# CCS811_breakout.net
KiCad netlist of a schematic drawn in EAGLE
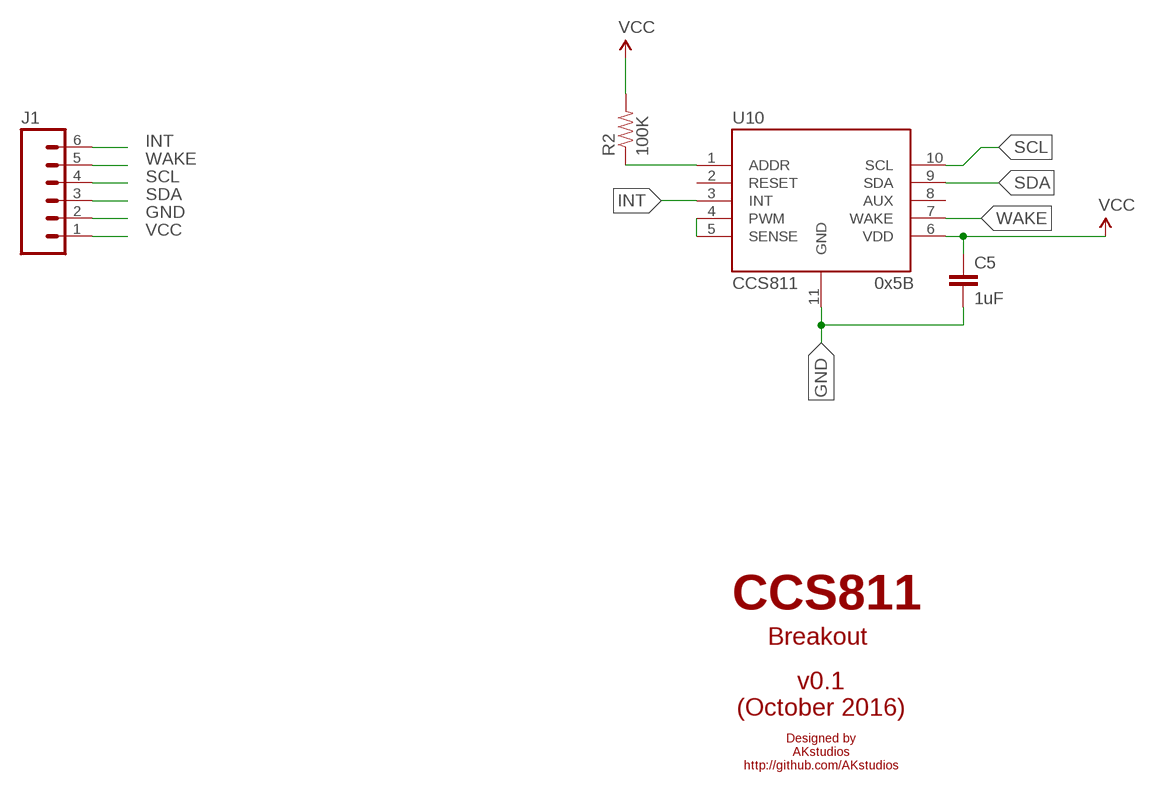
[diagram p0: schematic, sheet 1]

(export (version "E")
  (design (tool "Eeschema 10.0.6"))
  (components
    (comp (ref "C5")
      (value "1uF")
      (footprint "eagle-import:0805")
      (libsource (lib "eagle-import") (part "CAP0805"))
    )
    (comp (ref "J1")
      (value "M06SILK_FEMALE_PTH")
      (footprint "eagle-import:1X06")
      (libsource (lib "eagle-import") (part "M06SILK_FEMALE_PTH"))
    )
    (comp (ref "R2")
      (value "100K")
      (footprint "eagle-import:0805")
      (libsource (lib "eagle-import") (part "RESISTOR0805-RES"))
    )
    (comp (ref "U10")
      (value "CCS811")
      (footprint "eagle-import:LGA")
      (libsource (lib "eagle-import") (part "CCS811-I2C"))
    )
  )
  (nets
    (net (code "1") (name "GND") (class "Default")
      (node (ref "C5") (pin "2") (pinfunction "2_2") (pintype "passive"))
      (node (ref "J1") (pin "2") (pinfunction "2_2") (pintype "passive"))
      (node (ref "U10") (pin "11") (pinfunction "GND_11") (pintype "bidirectional"))
    )
    (net (code "2") (name "INT") (class "Default")
      (node (ref "J1") (pin "6") (pinfunction "6_6") (pintype "passive"))
      (node (ref "U10") (pin "3") (pinfunction "INT_3") (pintype "bidirectional"))
    )
    (net (code "3") (name "Net-(U10-ADDR)") (class "Default")
      (node (ref "R2") (pin "1") (pinfunction "1_1") (pintype "passive"))
      (node (ref "U10") (pin "1") (pinfunction "ADDR_1") (pintype "bidirectional"))
    )
    (net (code "4") (name "Net-(U10-PWM)") (class "Default")
      (node (ref "U10") (pin "4") (pinfunction "PWM_4") (pintype "bidirectional"))
      (node (ref "U10") (pin "5") (pinfunction "SENSE_5") (pintype "bidirectional"))
    )
    (net (code "5") (name "SCL") (class "Default")
      (node (ref "J1") (pin "4") (pinfunction "4_4") (pintype "passive"))
      (node (ref "U10") (pin "10") (pinfunction "SCL_10") (pintype "bidirectional"))
    )
    (net (code "6") (name "SDA") (class "Default")
      (node (ref "J1") (pin "3") (pinfunction "3_3") (pintype "passive"))
      (node (ref "U10") (pin "9") (pinfunction "SDA_9") (pintype "bidirectional"))
    )
    (net (code "7") (name "VCC") (class "Default")
      (node (ref "C5") (pin "1") (pinfunction "1_1") (pintype "passive"))
      (node (ref "J1") (pin "1") (pinfunction "1_1") (pintype "passive"))
      (node (ref "R2") (pin "2") (pinfunction "2_2") (pintype "passive"))
      (node (ref "U10") (pin "6") (pinfunction "VDD_6") (pintype "bidirectional"))
    )
    (net (code "8") (name "WAKE") (class "Default")
      (node (ref "J1") (pin "5") (pinfunction "5_5") (pintype "passive"))
      (node (ref "U10") (pin "7") (pinfunction "WAKE_7") (pintype "bidirectional"))
    )
    (net (code "9") (name "unconnected-(U10-AUX-Pad8)") (class "Default")
      (node (ref "U10") (pin "8") (pinfunction "AUX_8") (pintype "bidirectional"))
    )
    (net (code "10") (name "unconnected-(U10-RESET-Pad2)") (class "Default")
      (node (ref "U10") (pin "2") (pinfunction "RESET_2") (pintype "bidirectional"))
    )
  )
)
